# Boost_Converter.net
KiCad netlist of a schematic drawn in Altium Designer
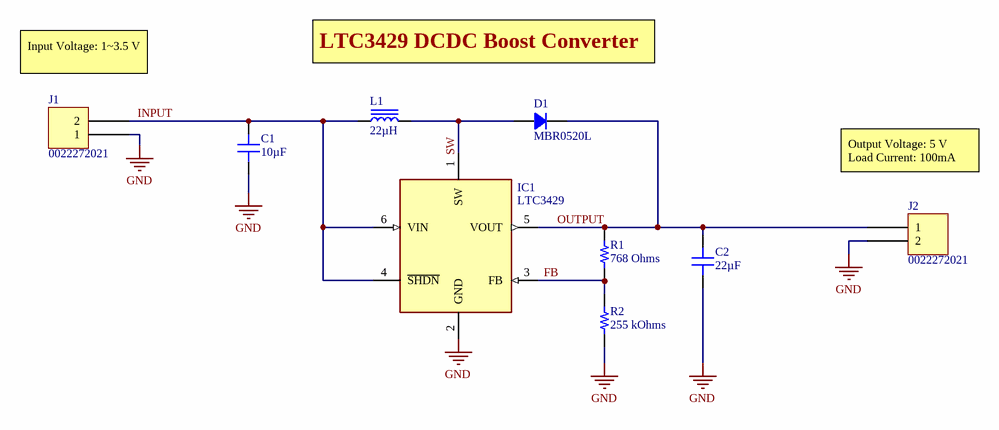
[diagram p0: Boost Converter.SchDoc]

(export (version "E")
  (design (tool "Eeschema 10.0.6"))
  (components
    (comp (ref "C1")
      (value "10µF")
      (footprint "CAP 0805_2012")
      (description "CAP CER 10UF 16V X6S 0805")
      (fields
        (field (name "PART NUMBER") "C2012X6S1C106K125AC")
        (field (name "MANUFACTURER") "TDK Corporation")
      )
      (libsource (lib "Celestial Altium Library - altium_library") (part "Capacitor"))
    )
    (comp (ref "C2")
      (value "22µF")
      (footprint "CAP 1206_3216 - 1.8MM")
      (description "CAP CER 22UF 16V X6S 1206")
      (fields
        (field (name "PART NUMBER") "CL31X226KOHN3NE")
        (field (name "MANUFACTURER") "Samsung Electro-Mechanics")
      )
      (libsource (lib "Celestial Altium Library - altium_library") (part "Capacitor"))
    )
    (comp (ref "D1")
      (value "MBR0520L")
      (footprint "SOD-123")
      (description "DIODE SCHOTTKY 20V 500MA SOD123")
      (fields (field (name "MANUFACTURER") "ON Semiconductor"))
      (libsource (lib "Celestial Altium Library - altium_library") (part "Diode"))
    )
    (comp (ref "IC1")
      (value "LTC3429")
      (footprint "SOT95P280X100-6N")
      (libsource (lib "SCH_Lib") (part "LTC3429ES6"))
    )
    (comp (ref "J1")
      (value "0022272021")
      (footprint "MOLEX KK 0022272021")
      (description "CONN HEADER VERT 2POS 2.54MM")
      (fields (field (name "MANUFACTURER") "Molex"))
      (libsource (lib "Celestial Altium Library - altium_library") (part "2 Pin"))
    )
    (comp (ref "J2")
      (value "0022272021")
      (footprint "MOLEX KK 0022272021")
      (description "CONN HEADER VERT 2POS 2.54MM")
      (fields (field (name "MANUFACTURER") "Molex"))
      (libsource (lib "") (part "2 Pin_1"))
    )
    (comp (ref "L1")
      (value "22µH")
      (footprint "TDK SLF7032")
      (description "FIXED IND 22UH 960MA 132 MOHM")
      (fields
        (field (name "PART NUMBER") "SLF7032T-220MR96-2PF")
        (field (name "MANUFACTURER") "TDK Corporation")
      )
      (libsource (lib "Celestial Altium Library - altium_library") (part "Inductor"))
    )
    (comp (ref "R1")
      (value "768 Ohms")
      (footprint "RES 0805_2012")
      (description "RES 768 OHM 1% 1/8W 0805")
      (fields
        (field (name "PART NUMBER") "RMCF0805FT768R")
        (field (name "MANUFACTURER") "Stackpole Electronics Inc")
      )
      (libsource (lib "Celestial Altium Library - altium_library") (part "Resistor"))
    )
    (comp (ref "R2")
      (value "255 kOhms")
      (footprint "RES 0805_2012")
      (description "RES SMD 255K OHM 0.1% 1/4W 0805")
      (fields
        (field (name "PART NUMBER") "3-2176094-2")
        (field (name "MANUFACTURER") "TE Connectivity Passive Product")
      )
      (libsource (lib "Celestial Altium Library - altium_library") (part "Resistor"))
    )
  )
  (nets
    (net (code "1") (name "/FB") (class "Default")
      (node (ref "IC1") (pin "3") (pinfunction "FB_3") (pintype "input"))
      (node (ref "R1") (pin "1") (pinfunction "1_1") (pintype "passive"))
      (node (ref "R2") (pin "2") (pinfunction "2_2") (pintype "passive"))
    )
    (net (code "2") (name "/INPUT") (class "Default")
      (node (ref "C1") (pin "2") (pinfunction "2_2") (pintype "passive"))
      (node (ref "IC1") (pin "4") (pinfunction "~{SHDN}_4") (pintype "passive"))
      (node (ref "IC1") (pin "6") (pinfunction "VIN_6") (pintype "input"))
      (node (ref "J1") (pin "2") (pinfunction "2_2") (pintype "passive"))
      (node (ref "L1") (pin "1") (pinfunction "1_1") (pintype "passive"))
    )
    (net (code "3") (name "/OUTPUT") (class "Default")
      (node (ref "C2") (pin "2") (pinfunction "2_2") (pintype "passive"))
      (node (ref "D1") (pin "2") (pinfunction "2_2") (pintype "passive"))
      (node (ref "IC1") (pin "5") (pinfunction "VOUT_5") (pintype "output"))
      (node (ref "J2") (pin "1") (pinfunction "1_1") (pintype "passive"))
      (node (ref "R1") (pin "2") (pinfunction "2_2") (pintype "passive"))
    )
    (net (code "5") (name "GND") (class "Default")
      (node (ref "C1") (pin "1") (pinfunction "1_1") (pintype "passive"))
      (node (ref "C2") (pin "1") (pinfunction "1_1") (pintype "passive"))
      (node (ref "IC1") (pin "2") (pinfunction "GND_2") (pintype "power_in"))
      (node (ref "J1") (pin "1") (pinfunction "1_1") (pintype "passive"))
      (node (ref "J2") (pin "2") (pinfunction "2_2") (pintype "passive"))
      (node (ref "R2") (pin "1") (pinfunction "1_1") (pintype "passive"))
    )
    (net (code "6") (name "Net-(IC1-SW)") (class "Default")
      (node (ref "D1") (pin "1") (pinfunction "1_1") (pintype "passive"))
      (node (ref "IC1") (pin "1") (pinfunction "SW_1") (pintype "passive"))
      (node (ref "L1") (pin "2") (pinfunction "2_2") (pintype "passive"))
    )
  )
)
